# Grownetics_3D_Crop_Sensor_Shield.net
KiCad netlist of a schematic drawn in EAGLE
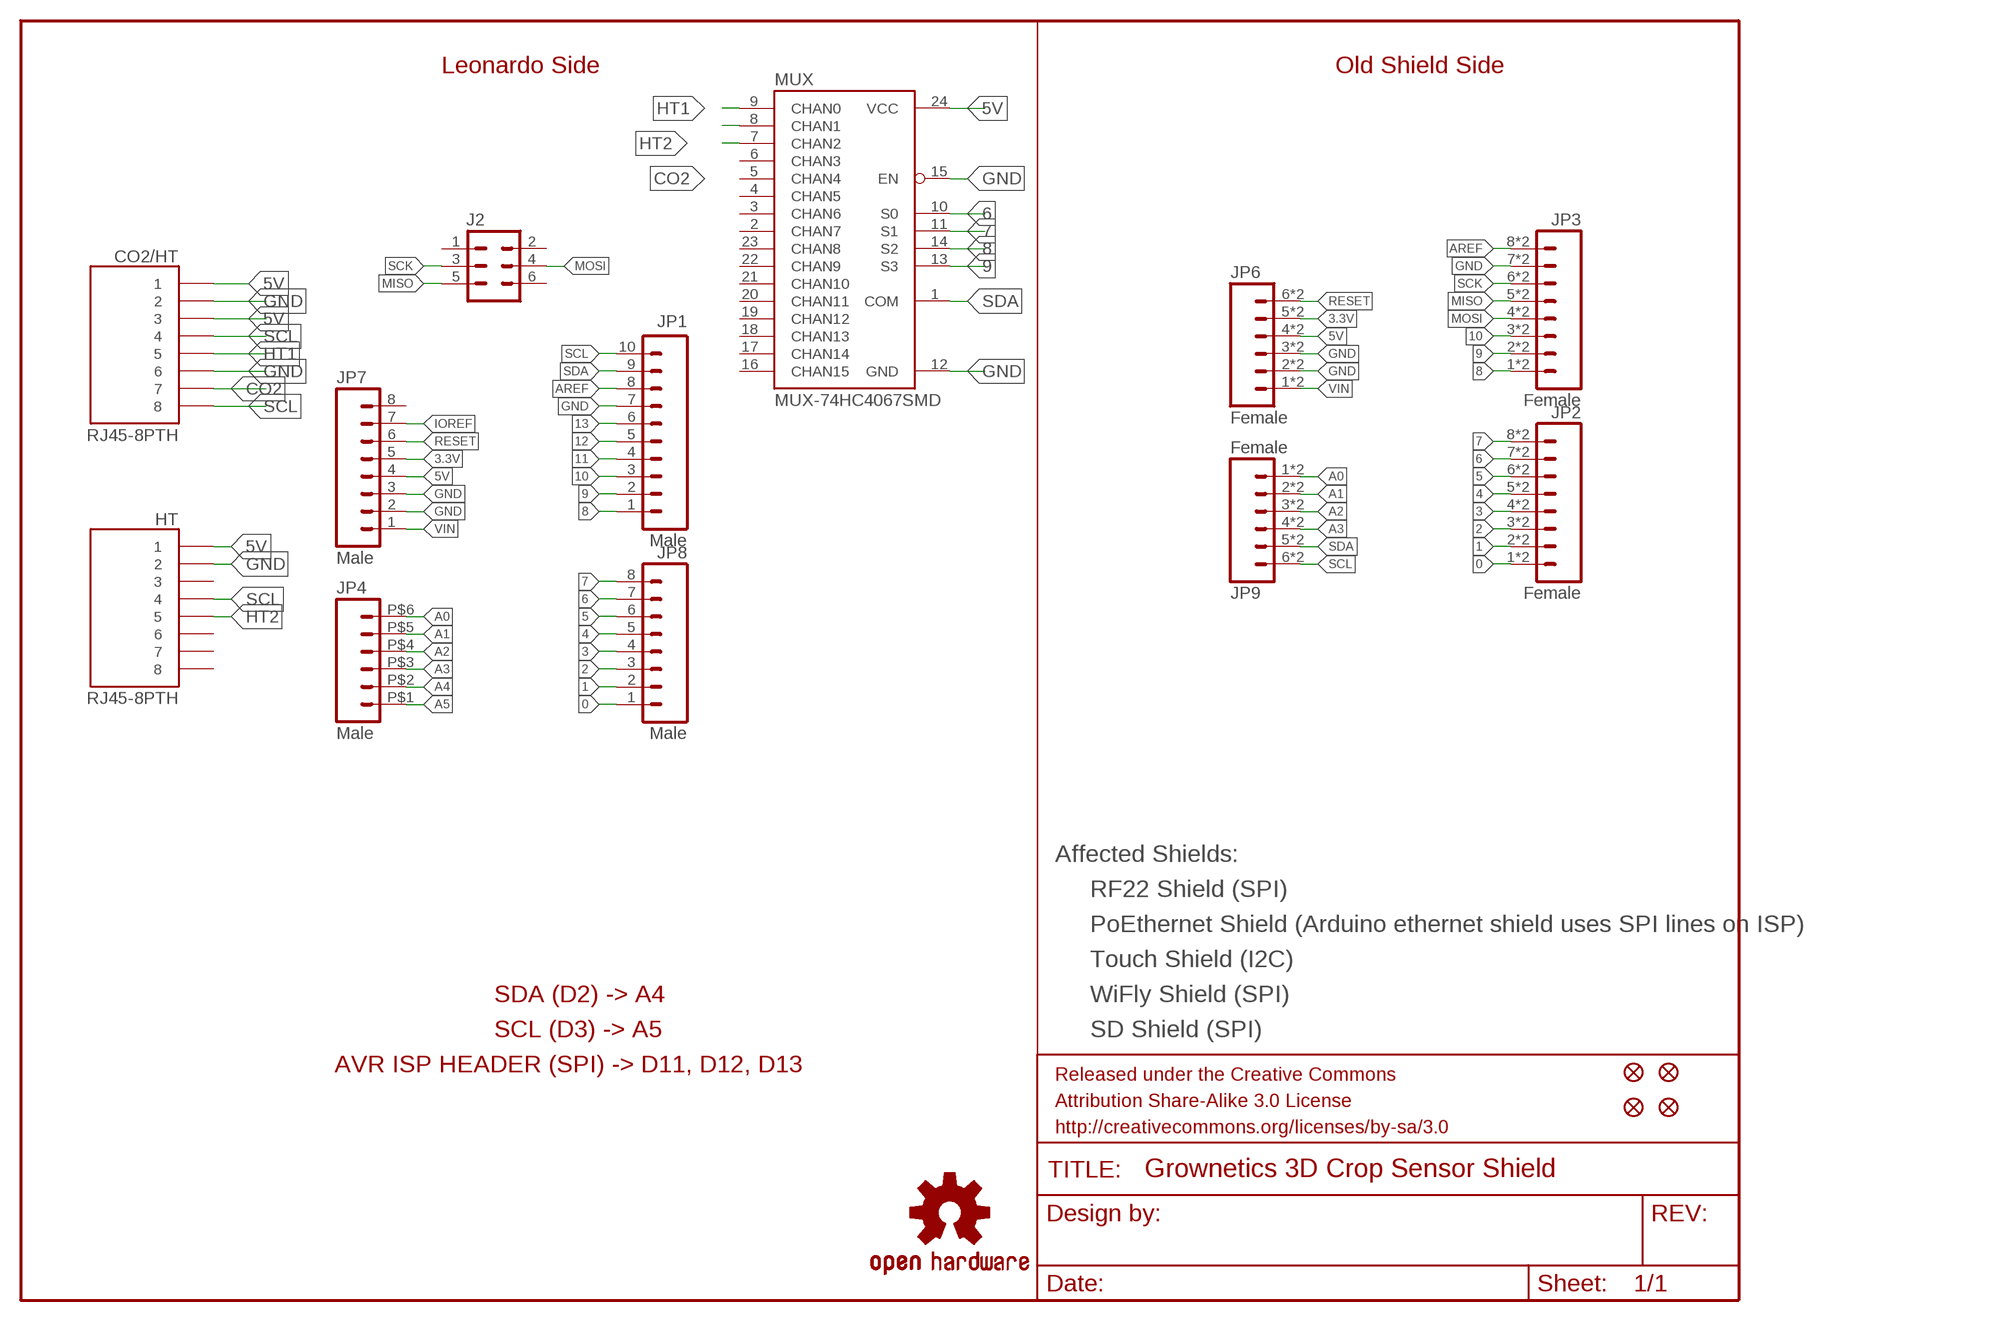
[diagram p0: schematic, sheet 1]

(export (version "E")
  (design (tool "Eeschema 10.0.6"))
  (components
    (comp (ref "CO2/HT")
      (value "RJ45-8PTH")
      (footprint "eagle-import:RJ45-8")
      (libsource (lib "eagle-import") (part "RJ45-8PTH"))
    )
    (comp (ref "HT")
      (value "RJ45-8PTH")
      (footprint "eagle-import:RJ45-8")
      (libsource (lib "eagle-import") (part "RJ45-8PTH"))
    )
    (comp (ref "J2")
      (value "Female")
      (footprint "eagle-import:2X3_SMD")
      (libsource (lib "eagle-import") (part "M03X2"))
    )
    (comp (ref "JP1")
      (value "Male")
      (footprint "eagle-import:1X10_SMD_MALE")
      (libsource (lib "eagle-import") (part "M10SMD_MALE"))
    )
    (comp (ref "JP2")
      (value "Female")
      (footprint "eagle-import:1X08_SMD_COMBINED")
      (libsource (lib "eagle-import") (part "M08SMD-COMBO"))
    )
    (comp (ref "JP3")
      (value "Female")
      (footprint "eagle-import:1X08_SMD_COMBINED")
      (libsource (lib "eagle-import") (part "M08SMD-COMBO"))
    )
    (comp (ref "JP4")
      (value "Male")
      (footprint "eagle-import:1X06_SMD_MALE")
      (libsource (lib "eagle-import") (part "M06SMD_MALE"))
    )
    (comp (ref "JP6")
      (value "Female")
      (footprint "eagle-import:1X06_SMD_STRAIGHT_COMBO")
      (libsource (lib "eagle-import") (part "M06SMD-STRAIGHT-COMBO"))
    )
    (comp (ref "JP7")
      (value "Male")
      (footprint "eagle-import:1X08_SMD_MALE")
      (libsource (lib "eagle-import") (part "M08SMD-MALE"))
    )
    (comp (ref "JP8")
      (value "Male")
      (footprint "eagle-import:1X08_SMD_MALE")
      (libsource (lib "eagle-import") (part "M08SMD-MALE"))
    )
    (comp (ref "JP9")
      (value "Female")
      (footprint "eagle-import:1X06_SMD_STRAIGHT_COMBO")
      (libsource (lib "eagle-import") (part "M06SMD-STRAIGHT-COMBO"))
    )
    (comp (ref "JP11")
      (value "FIDUCIALUFIDUCIAL")
      (footprint "eagle-import:MICRO-FIDUCIAL")
      (libsource (lib "eagle-import") (part "FIDUCIALUFIDUCIAL"))
    )
    (comp (ref "JP12")
      (value "FIDUCIALUFIDUCIAL")
      (footprint "eagle-import:MICRO-FIDUCIAL")
      (libsource (lib "eagle-import") (part "FIDUCIALUFIDUCIAL"))
    )
    (comp (ref "JP13")
      (value "FIDUCIALUFIDUCIAL")
      (footprint "eagle-import:MICRO-FIDUCIAL")
      (libsource (lib "eagle-import") (part "FIDUCIALUFIDUCIAL"))
    )
    (comp (ref "JP14")
      (value "FIDUCIALUFIDUCIAL")
      (footprint "eagle-import:MICRO-FIDUCIAL")
      (libsource (lib "eagle-import") (part "FIDUCIALUFIDUCIAL"))
    )
    (comp (ref "MUX")
      (value "MUX-74HC4067SMD")
      (footprint "eagle-import:SSOP24")
      (libsource (lib "eagle-import") (part "MUX-74HC4067SMD"))
    )
    (comp (ref "U$1")
      (value "OSHW-LOGOS")
      (footprint "eagle-import:OSHW-LOGO-S")
      (libsource (lib "eagle-import") (part "OSHW-LOGOS"))
    )
  )
  (nets
    (net (code "1") (name "0") (class "Default")
      (node (ref "JP2") (pin "1") (pinfunction "1_1") (pintype "passive"))
      (node (ref "JP2") (pin "1@2") (pinfunction "1_1@2") (pintype "passive"))
      (node (ref "JP8") (pin "1") (pinfunction "1_1") (pintype "passive"))
    )
    (net (code "2") (name "1") (class "Default")
      (node (ref "JP2") (pin "2") (pinfunction "2_2") (pintype "passive"))
      (node (ref "JP2") (pin "2@2") (pinfunction "2_2@2") (pintype "passive"))
      (node (ref "JP8") (pin "2") (pinfunction "2_2") (pintype "passive"))
    )
    (net (code "3") (name "2") (class "Default")
      (node (ref "JP2") (pin "3") (pinfunction "3_3") (pintype "passive"))
      (node (ref "JP2") (pin "3@2") (pinfunction "3_3@2") (pintype "passive"))
      (node (ref "JP8") (pin "3") (pinfunction "3_3") (pintype "passive"))
    )
    (net (code "4") (name "3") (class "Default")
      (node (ref "JP2") (pin "4") (pinfunction "4_4") (pintype "passive"))
      (node (ref "JP2") (pin "4@2") (pinfunction "4_4@2") (pintype "passive"))
      (node (ref "JP8") (pin "4") (pinfunction "4_4") (pintype "passive"))
    )
    (net (code "5") (name "3.3V") (class "Default")
      (node (ref "JP6") (pin "5") (pinfunction "5_5") (pintype "passive"))
      (node (ref "JP6") (pin "5-2") (pinfunction "5_5-2") (pintype "passive"))
      (node (ref "JP7") (pin "5") (pinfunction "5_5") (pintype "passive"))
    )
    (net (code "6") (name "4") (class "Default")
      (node (ref "JP2") (pin "5") (pinfunction "5_5") (pintype "passive"))
      (node (ref "JP2") (pin "5@2") (pinfunction "5_5@2") (pintype "passive"))
      (node (ref "JP8") (pin "5") (pinfunction "5_5") (pintype "passive"))
    )
    (net (code "7") (name "5") (class "Default")
      (node (ref "JP2") (pin "6") (pinfunction "6_6") (pintype "passive"))
      (node (ref "JP2") (pin "6@2") (pinfunction "6_6@2") (pintype "passive"))
      (node (ref "JP8") (pin "6") (pinfunction "6_6") (pintype "passive"))
    )
    (net (code "8") (name "5V") (class "Default")
      (node (ref "CO2/HT") (pin "1") (pinfunction "1_1") (pintype "bidirectional"))
      (node (ref "CO2/HT") (pin "3") (pinfunction "3_3") (pintype "bidirectional"))
      (node (ref "HT") (pin "1") (pinfunction "1_1") (pintype "bidirectional"))
      (node (ref "JP6") (pin "4") (pinfunction "4_4") (pintype "passive"))
      (node (ref "JP6") (pin "4-2") (pinfunction "4_4-2") (pintype "passive"))
      (node (ref "JP7") (pin "4") (pinfunction "4_4") (pintype "passive"))
      (node (ref "MUX") (pin "24") (pinfunction "VCC_24") (pintype "bidirectional"))
    )
    (net (code "9") (name "6") (class "Default")
      (node (ref "JP2") (pin "7") (pinfunction "7_7") (pintype "passive"))
      (node (ref "JP2") (pin "7@2") (pinfunction "7_7@2") (pintype "passive"))
      (node (ref "JP8") (pin "7") (pinfunction "7_7") (pintype "passive"))
      (node (ref "MUX") (pin "10") (pinfunction "S0_10") (pintype "input"))
    )
    (net (code "10") (name "7") (class "Default")
      (node (ref "JP2") (pin "8") (pinfunction "8_8") (pintype "passive"))
      (node (ref "JP2") (pin "8@2") (pinfunction "8_8@2") (pintype "passive"))
      (node (ref "JP8") (pin "8") (pinfunction "8_8") (pintype "passive"))
      (node (ref "MUX") (pin "11") (pinfunction "S1_11") (pintype "input"))
    )
    (net (code "11") (name "8") (class "Default")
      (node (ref "JP1") (pin "1") (pinfunction "1_1") (pintype "passive"))
      (node (ref "JP3") (pin "1") (pinfunction "1_1") (pintype "passive"))
      (node (ref "JP3") (pin "1@2") (pinfunction "1_1@2") (pintype "passive"))
      (node (ref "MUX") (pin "14") (pinfunction "S2_14") (pintype "input"))
    )
    (net (code "12") (name "9") (class "Default")
      (node (ref "JP1") (pin "2") (pinfunction "2_2") (pintype "passive"))
      (node (ref "JP3") (pin "2") (pinfunction "2_2") (pintype "passive"))
      (node (ref "JP3") (pin "2@2") (pinfunction "2_2@2") (pintype "passive"))
      (node (ref "MUX") (pin "13") (pinfunction "S3_13") (pintype "input"))
    )
    (net (code "13") (name "10") (class "Default")
      (node (ref "JP1") (pin "3") (pinfunction "3_3") (pintype "passive"))
      (node (ref "JP3") (pin "3") (pinfunction "3_3") (pintype "passive"))
      (node (ref "JP3") (pin "3@2") (pinfunction "3_3@2") (pintype "passive"))
    )
    (net (code "14") (name "11") (class "Default")
      (node (ref "JP1") (pin "4") (pinfunction "4_4") (pintype "passive"))
    )
    (net (code "15") (name "12") (class "Default")
      (node (ref "JP1") (pin "5") (pinfunction "5_5") (pintype "passive"))
    )
    (net (code "16") (name "13") (class "Default")
      (node (ref "JP1") (pin "6") (pinfunction "6_6") (pintype "passive"))
    )
    (net (code "17") (name "A0") (class "Default")
      (node (ref "JP4") (pin "P$6") (pinfunction "6_P$6") (pintype "passive"))
      (node (ref "JP9") (pin "1") (pinfunction "1_1") (pintype "passive"))
      (node (ref "JP9") (pin "1-2") (pinfunction "1_1-2") (pintype "passive"))
    )
    (net (code "18") (name "A1") (class "Default")
      (node (ref "JP4") (pin "P$5") (pinfunction "5_P$5") (pintype "passive"))
      (node (ref "JP9") (pin "2") (pinfunction "2_2") (pintype "passive"))
      (node (ref "JP9") (pin "2-2") (pinfunction "2_2-2") (pintype "passive"))
    )
    (net (code "19") (name "A2") (class "Default")
      (node (ref "JP4") (pin "P$4") (pinfunction "4_P$4") (pintype "passive"))
      (node (ref "JP9") (pin "3") (pinfunction "3_3") (pintype "passive"))
      (node (ref "JP9") (pin "3-2") (pinfunction "3_3-2") (pintype "passive"))
    )
    (net (code "20") (name "A3") (class "Default")
      (node (ref "JP4") (pin "P$3") (pinfunction "3_P$3") (pintype "passive"))
      (node (ref "JP9") (pin "4") (pinfunction "4_4") (pintype "passive"))
      (node (ref "JP9") (pin "4-2") (pinfunction "4_4-2") (pintype "passive"))
    )
    (net (code "21") (name "A4") (class "Default")
      (node (ref "JP4") (pin "P$2") (pinfunction "2_P$2") (pintype "passive"))
    )
    (net (code "22") (name "A5") (class "Default")
      (node (ref "JP4") (pin "P$1") (pinfunction "1_P$1") (pintype "passive"))
    )
    (net (code "23") (name "AREF") (class "Default")
      (node (ref "JP1") (pin "8") (pinfunction "8_8") (pintype "passive"))
      (node (ref "JP3") (pin "8") (pinfunction "8_8") (pintype "passive"))
      (node (ref "JP3") (pin "8@2") (pinfunction "8_8@2") (pintype "passive"))
    )
    (net (code "24") (name "CO2") (class "Default")
      (node (ref "CO2/HT") (pin "7") (pinfunction "7_7") (pintype "bidirectional"))
      (node (ref "MUX") (pin "7") (pinfunction "CHAN2_7") (pintype "bidirectional"))
    )
    (net (code "25") (name "GND") (class "Default")
      (node (ref "CO2/HT") (pin "2") (pinfunction "2_2") (pintype "bidirectional"))
      (node (ref "CO2/HT") (pin "6") (pinfunction "6_6") (pintype "bidirectional"))
      (node (ref "HT") (pin "2") (pinfunction "2_2") (pintype "bidirectional"))
      (node (ref "JP1") (pin "7") (pinfunction "7_7") (pintype "passive"))
      (node (ref "JP3") (pin "7") (pinfunction "7_7") (pintype "passive"))
      (node (ref "JP3") (pin "7@2") (pinfunction "7_7@2") (pintype "passive"))
      (node (ref "JP6") (pin "2") (pinfunction "2_2") (pintype "passive"))
      (node (ref "JP6") (pin "2-2") (pinfunction "2_2-2") (pintype "passive"))
      (node (ref "JP6") (pin "3") (pinfunction "3_3") (pintype "passive"))
      (node (ref "JP6") (pin "3-2") (pinfunction "3_3-2") (pintype "passive"))
      (node (ref "JP7") (pin "2") (pinfunction "2_2") (pintype "passive"))
      (node (ref "JP7") (pin "3") (pinfunction "3_3") (pintype "passive"))
      (node (ref "MUX") (pin "12") (pinfunction "GND_12") (pintype "bidirectional"))
      (node (ref "MUX") (pin "15") (pinfunction "EN_15") (pintype "input"))
    )
    (net (code "26") (name "HT1") (class "Default")
      (node (ref "CO2/HT") (pin "5") (pinfunction "5_5") (pintype "bidirectional"))
      (node (ref "MUX") (pin "9") (pinfunction "CHAN0_9") (pintype "bidirectional"))
    )
    (net (code "27") (name "HT2") (class "Default")
      (node (ref "HT") (pin "5") (pinfunction "5_5") (pintype "bidirectional"))
      (node (ref "MUX") (pin "8") (pinfunction "CHAN1_8") (pintype "bidirectional"))
    )
    (net (code "28") (name "IOREF") (class "Default")
      (node (ref "JP7") (pin "7") (pinfunction "7_7") (pintype "passive"))
    )
    (net (code "29") (name "MISO") (class "Default")
      (node (ref "J2") (pin "5") (pinfunction "5_5") (pintype "passive"))
      (node (ref "JP3") (pin "5") (pinfunction "5_5") (pintype "passive"))
      (node (ref "JP3") (pin "5@2") (pinfunction "5_5@2") (pintype "passive"))
    )
    (net (code "30") (name "MOSI") (class "Default")
      (node (ref "J2") (pin "4") (pinfunction "4_4") (pintype "passive"))
      (node (ref "JP3") (pin "4") (pinfunction "4_4") (pintype "passive"))
      (node (ref "JP3") (pin "4@2") (pinfunction "4_4@2") (pintype "passive"))
    )
    (net (code "31") (name "RESET") (class "Default")
      (node (ref "JP6") (pin "6") (pinfunction "6_6") (pintype "passive"))
      (node (ref "JP6") (pin "6-2") (pinfunction "6_6-2") (pintype "passive"))
      (node (ref "JP7") (pin "6") (pinfunction "6_6") (pintype "passive"))
    )
    (net (code "32") (name "SCK") (class "Default")
      (node (ref "J2") (pin "3") (pinfunction "3_3") (pintype "passive"))
      (node (ref "JP3") (pin "6") (pinfunction "6_6") (pintype "passive"))
      (node (ref "JP3") (pin "6@2") (pinfunction "6_6@2") (pintype "passive"))
    )
    (net (code "33") (name "SCL") (class "Default")
      (node (ref "CO2/HT") (pin "4") (pinfunction "4_4") (pintype "bidirectional"))
      (node (ref "CO2/HT") (pin "8") (pinfunction "8_8") (pintype "bidirectional"))
      (node (ref "HT") (pin "4") (pinfunction "4_4") (pintype "bidirectional"))
      (node (ref "JP1") (pin "10") (pinfunction "10_10") (pintype "passive"))
      (node (ref "JP9") (pin "6") (pinfunction "6_6") (pintype "passive"))
      (node (ref "JP9") (pin "6-2") (pinfunction "6_6-2") (pintype "passive"))
    )
    (net (code "34") (name "SDA") (class "Default")
      (node (ref "JP1") (pin "9") (pinfunction "9_9") (pintype "passive"))
      (node (ref "JP9") (pin "5") (pinfunction "5_5") (pintype "passive"))
      (node (ref "JP9") (pin "5-2") (pinfunction "5_5-2") (pintype "passive"))
      (node (ref "MUX") (pin "1") (pinfunction "COM_1") (pintype "bidirectional"))
    )
    (net (code "35") (name "VIN") (class "Default")
      (node (ref "JP6") (pin "1") (pinfunction "1_1") (pintype "passive"))
      (node (ref "JP6") (pin "1-2") (pinfunction "1_1-2") (pintype "passive"))
      (node (ref "JP7") (pin "1") (pinfunction "1_1") (pintype "passive"))
    )
    (net (code "36") (name "unconnected-(HT-Pad3)") (class "Default")
      (node (ref "HT") (pin "3") (pinfunction "3_3") (pintype "bidirectional"))
    )
    (net (code "37") (name "unconnected-(HT-Pad6)") (class "Default")
      (node (ref "HT") (pin "6") (pinfunction "6_6") (pintype "bidirectional"))
    )
    (net (code "38") (name "unconnected-(HT-Pad7)") (class "Default")
      (node (ref "HT") (pin "7") (pinfunction "7_7") (pintype "bidirectional"))
    )
    (net (code "39") (name "unconnected-(HT-Pad8)") (class "Default")
      (node (ref "HT") (pin "8") (pinfunction "8_8") (pintype "bidirectional"))
    )
    (net (code "40") (name "unconnected-(J2-Pad1)") (class "Default")
      (node (ref "J2") (pin "1") (pinfunction "1_1") (pintype "passive"))
    )
    (net (code "41") (name "unconnected-(J2-Pad2)") (class "Default")
      (node (ref "J2") (pin "2") (pinfunction "2_2") (pintype "passive"))
    )
    (net (code "42") (name "unconnected-(J2-Pad6)") (class "Default")
      (node (ref "J2") (pin "6") (pinfunction "6_6") (pintype "passive"))
    )
    (net (code "43") (name "unconnected-(JP7-Pad8)") (class "Default")
      (node (ref "JP7") (pin "8") (pinfunction "8_8") (pintype "passive"))
    )
    (net (code "44") (name "unconnected-(MUX-CHAN3-Pad6)") (class "Default")
      (node (ref "MUX") (pin "6") (pinfunction "CHAN3_6") (pintype "bidirectional"))
    )
    (net (code "45") (name "unconnected-(MUX-CHAN4-Pad5)") (class "Default")
      (node (ref "MUX") (pin "5") (pinfunction "CHAN4_5") (pintype "bidirectional"))
    )
    (net (code "46") (name "unconnected-(MUX-CHAN5-Pad4)") (class "Default")
      (node (ref "MUX") (pin "4") (pinfunction "CHAN5_4") (pintype "bidirectional"))
    )
    (net (code "47") (name "unconnected-(MUX-CHAN6-Pad3)") (class "Default")
      (node (ref "MUX") (pin "3") (pinfunction "CHAN6_3") (pintype "bidirectional"))
    )
    (net (code "48") (name "unconnected-(MUX-CHAN7-Pad2)") (class "Default")
      (node (ref "MUX") (pin "2") (pinfunction "CHAN7_2") (pintype "bidirectional"))
    )
    (net (code "49") (name "unconnected-(MUX-CHAN8-Pad23)") (class "Default")
      (node (ref "MUX") (pin "23") (pinfunction "CHAN8_23") (pintype "bidirectional"))
    )
    (net (code "50") (name "unconnected-(MUX-CHAN9-Pad22)") (class "Default")
      (node (ref "MUX") (pin "22") (pinfunction "CHAN9_22") (pintype "bidirectional"))
    )
    (net (code "51") (name "unconnected-(MUX-CHAN10-Pad21)") (class "Default")
      (node (ref "MUX") (pin "21") (pinfunction "CHAN10_21") (pintype "bidirectional"))
    )
    (net (code "52") (name "unconnected-(MUX-CHAN11-Pad20)") (class "Default")
      (node (ref "MUX") (pin "20") (pinfunction "CHAN11_20") (pintype "bidirectional"))
    )
    (net (code "53") (name "unconnected-(MUX-CHAN12-Pad19)") (class "Default")
      (node (ref "MUX") (pin "19") (pinfunction "CHAN12_19") (pintype "bidirectional"))
    )
    (net (code "54") (name "unconnected-(MUX-CHAN13-Pad18)") (class "Default")
      (node (ref "MUX") (pin "18") (pinfunction "CHAN13_18") (pintype "bidirectional"))
    )
    (net (code "55") (name "unconnected-(MUX-CHAN14-Pad17)") (class "Default")
      (node (ref "MUX") (pin "17") (pinfunction "CHAN14_17") (pintype "bidirectional"))
    )
    (net (code "56") (name "unconnected-(MUX-CHAN15-Pad16)") (class "Default")
      (node (ref "MUX") (pin "16") (pinfunction "CHAN15_16") (pintype "bidirectional"))
    )
  )
)
